# QSTL_Nano_D_Con_Micro_DSUB.net
KiCad netlist of a schematic drawn in Altium Designer
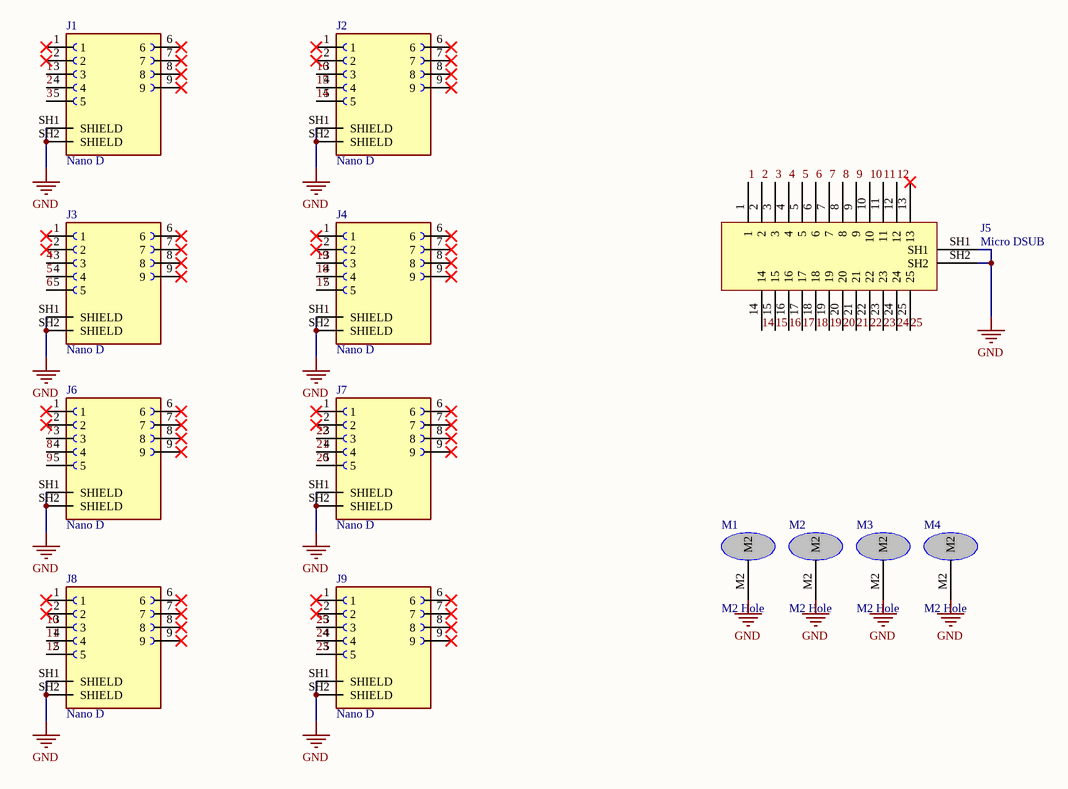
[diagram p0: QSTL_Nano_D_Con_Micro_DSUB.SchDoc]

(export (version "E")
  (design (tool "Eeschema 10.0.6"))
  (components
    (comp (ref "J1")
      (value "Nano D")
      (footprint "A29500-009")
      (description "https://www.digikey.ca/en/products/detail/omnetics/A29500-009/16614880")
      (libsource (lib "QSTL_Nano_D_Con_Micro_DSUB") (part "A29500-009"))
    )
    (comp (ref "J2")
      (value "Nano D")
      (footprint "A29500-009")
      (description "https://www.digikey.ca/en/products/detail/omnetics/A29500-009/16614880")
      (libsource (lib "QSTL_Nano_D_Con_Micro_DSUB") (part "A29500-009"))
    )
    (comp (ref "J3")
      (value "Nano D")
      (footprint "A29500-009")
      (description "https://www.digikey.ca/en/products/detail/omnetics/A29500-009/16614880")
      (libsource (lib "QSTL_Nano_D_Con_Micro_DSUB") (part "A29500-009"))
    )
    (comp (ref "J4")
      (value "Nano D")
      (footprint "A29500-009")
      (description "https://www.digikey.ca/en/products/detail/omnetics/A29500-009/16614880")
      (libsource (lib "QSTL_Nano_D_Con_Micro_DSUB") (part "A29500-009"))
    )
    (comp (ref "J5")
      (value "Micro DSUB")
      (footprint "380-025-113L001")
      (description "NorComp Plug Micro DSUB")
      (libsource (lib "QSTL_Nano_D_Con_Micro_DSUB") (part "380-025-113L001"))
    )
    (comp (ref "J6")
      (value "Nano D")
      (footprint "A29500-009")
      (description "https://www.digikey.ca/en/products/detail/omnetics/A29500-009/16614880")
      (libsource (lib "QSTL_Nano_D_Con_Micro_DSUB") (part "A29500-009"))
    )
    (comp (ref "J7")
      (value "Nano D")
      (footprint "A29500-009")
      (description "https://www.digikey.ca/en/products/detail/omnetics/A29500-009/16614880")
      (libsource (lib "QSTL_Nano_D_Con_Micro_DSUB") (part "A29500-009"))
    )
    (comp (ref "J8")
      (value "Nano D")
      (footprint "A29500-009")
      (description "https://www.digikey.ca/en/products/detail/omnetics/A29500-009/16614880")
      (libsource (lib "QSTL_Nano_D_Con_Micro_DSUB") (part "A29500-009"))
    )
    (comp (ref "J9")
      (value "Nano D")
      (footprint "A29500-009")
      (description "https://www.digikey.ca/en/products/detail/omnetics/A29500-009/16614880")
      (libsource (lib "QSTL_Nano_D_Con_Micro_DSUB") (part "A29500-009"))
    )
    (comp (ref "M1")
      (value "M2 Hole")
      (footprint "M2_Hole")
      (libsource (lib "QSTL_Nano_D_Con_Micro_DSUB") (part "M2_Hole"))
    )
    (comp (ref "M2")
      (value "M2 Hole")
      (footprint "M2_Hole")
      (libsource (lib "QSTL_Nano_D_Con_Micro_DSUB") (part "M2_Hole"))
    )
    (comp (ref "M3")
      (value "M2 Hole")
      (footprint "M2_Hole")
      (libsource (lib "QSTL_Nano_D_Con_Micro_DSUB") (part "M2_Hole"))
    )
    (comp (ref "M4")
      (value "M2 Hole")
      (footprint "M2_Hole")
      (libsource (lib "QSTL_Nano_D_Con_Micro_DSUB") (part "M2_Hole"))
    )
  )
  (nets
    (net (code "1") (name "/1") (class "Default")
      (node (ref "J1") (pin "3") (pinfunction "3_3") (pintype "passive"))
      (node (ref "J5") (pin "1") (pinfunction "1_1") (pintype "passive"))
    )
    (net (code "2") (name "/2") (class "Default")
      (node (ref "J1") (pin "4") (pinfunction "4_4") (pintype "passive"))
      (node (ref "J5") (pin "2") (pinfunction "2_2") (pintype "passive"))
    )
    (net (code "3") (name "/3") (class "Default")
      (node (ref "J1") (pin "5") (pinfunction "5_5") (pintype "passive"))
      (node (ref "J5") (pin "3") (pinfunction "3_3") (pintype "passive"))
    )
    (net (code "4") (name "/4") (class "Default")
      (node (ref "J3") (pin "3") (pinfunction "3_3") (pintype "passive"))
      (node (ref "J5") (pin "4") (pinfunction "4_4") (pintype "passive"))
    )
    (net (code "5") (name "/5") (class "Default")
      (node (ref "J3") (pin "4") (pinfunction "4_4") (pintype "passive"))
      (node (ref "J5") (pin "5") (pinfunction "5_5") (pintype "passive"))
    )
    (net (code "6") (name "/6") (class "Default")
      (node (ref "J3") (pin "5") (pinfunction "5_5") (pintype "passive"))
      (node (ref "J5") (pin "6") (pinfunction "6_6") (pintype "passive"))
    )
    (net (code "7") (name "/7") (class "Default")
      (node (ref "J5") (pin "7") (pinfunction "7_7") (pintype "passive"))
      (node (ref "J6") (pin "3") (pinfunction "3_3") (pintype "passive"))
    )
    (net (code "8") (name "/8") (class "Default")
      (node (ref "J5") (pin "8") (pinfunction "8_8") (pintype "passive"))
      (node (ref "J6") (pin "4") (pinfunction "4_4") (pintype "passive"))
    )
    (net (code "9") (name "/9") (class "Default")
      (node (ref "J5") (pin "9") (pinfunction "9_9") (pintype "passive"))
      (node (ref "J6") (pin "5") (pinfunction "5_5") (pintype "passive"))
    )
    (net (code "10") (name "/10") (class "Default")
      (node (ref "J5") (pin "10") (pinfunction "10_10") (pintype "passive"))
      (node (ref "J8") (pin "3") (pinfunction "3_3") (pintype "passive"))
    )
    (net (code "11") (name "/11") (class "Default")
      (node (ref "J5") (pin "11") (pinfunction "11_11") (pintype "passive"))
      (node (ref "J8") (pin "4") (pinfunction "4_4") (pintype "passive"))
    )
    (net (code "12") (name "/12") (class "Default")
      (node (ref "J5") (pin "12") (pinfunction "12_12") (pintype "passive"))
      (node (ref "J8") (pin "5") (pinfunction "5_5") (pintype "passive"))
    )
    (net (code "13") (name "/14") (class "Default")
      (node (ref "J2") (pin "5") (pinfunction "5_5") (pintype "passive"))
      (node (ref "J5") (pin "14") (pinfunction "14_14") (pintype "passive"))
    )
    (net (code "14") (name "/15") (class "Default")
      (node (ref "J2") (pin "4") (pinfunction "4_4") (pintype "passive"))
      (node (ref "J5") (pin "15") (pinfunction "15_15") (pintype "passive"))
    )
    (net (code "15") (name "/16") (class "Default")
      (node (ref "J2") (pin "3") (pinfunction "3_3") (pintype "passive"))
      (node (ref "J5") (pin "16") (pinfunction "16_16") (pintype "passive"))
    )
    (net (code "16") (name "/17") (class "Default")
      (node (ref "J4") (pin "5") (pinfunction "5_5") (pintype "passive"))
      (node (ref "J5") (pin "17") (pinfunction "17_17") (pintype "passive"))
    )
    (net (code "17") (name "/18") (class "Default")
      (node (ref "J4") (pin "4") (pinfunction "4_4") (pintype "passive"))
      (node (ref "J5") (pin "18") (pinfunction "18_18") (pintype "passive"))
    )
    (net (code "18") (name "/19") (class "Default")
      (node (ref "J4") (pin "3") (pinfunction "3_3") (pintype "passive"))
      (node (ref "J5") (pin "19") (pinfunction "19_19") (pintype "passive"))
    )
    (net (code "19") (name "/20") (class "Default")
      (node (ref "J5") (pin "20") (pinfunction "20_20") (pintype "passive"))
      (node (ref "J7") (pin "5") (pinfunction "5_5") (pintype "passive"))
    )
    (net (code "20") (name "/21") (class "Default")
      (node (ref "J5") (pin "21") (pinfunction "21_21") (pintype "passive"))
      (node (ref "J7") (pin "4") (pinfunction "4_4") (pintype "passive"))
    )
    (net (code "21") (name "/22") (class "Default")
      (node (ref "J5") (pin "22") (pinfunction "22_22") (pintype "passive"))
      (node (ref "J7") (pin "3") (pinfunction "3_3") (pintype "passive"))
    )
    (net (code "22") (name "/23") (class "Default")
      (node (ref "J5") (pin "23") (pinfunction "23_23") (pintype "passive"))
      (node (ref "J9") (pin "5") (pinfunction "5_5") (pintype "passive"))
    )
    (net (code "23") (name "/24") (class "Default")
      (node (ref "J5") (pin "24") (pinfunction "24_24") (pintype "passive"))
      (node (ref "J9") (pin "4") (pinfunction "4_4") (pintype "passive"))
    )
    (net (code "24") (name "/25") (class "Default")
      (node (ref "J5") (pin "25") (pinfunction "25_25") (pintype "passive"))
      (node (ref "J9") (pin "3") (pinfunction "3_3") (pintype "passive"))
    )
    (net (code "25") (name "GND") (class "Default")
      (node (ref "J1") (pin "SH1") (pinfunction "SHIELD_SH1") (pintype "passive"))
      (node (ref "J1") (pin "SH2") (pinfunction "SHIELD_SH2") (pintype "passive"))
      (node (ref "J2") (pin "SH1") (pinfunction "SHIELD_SH1") (pintype "passive"))
      (node (ref "J2") (pin "SH2") (pinfunction "SHIELD_SH2") (pintype "passive"))
      (node (ref "J3") (pin "SH1") (pinfunction "SHIELD_SH1") (pintype "passive"))
      (node (ref "J3") (pin "SH2") (pinfunction "SHIELD_SH2") (pintype "passive"))
      (node (ref "J4") (pin "SH1") (pinfunction "SHIELD_SH1") (pintype "passive"))
      (node (ref "J4") (pin "SH2") (pinfunction "SHIELD_SH2") (pintype "passive"))
      (node (ref "J5") (pin "SH1") (pinfunction "SH1_SH1") (pintype "passive"))
      (node (ref "J5") (pin "SH2") (pinfunction "SH2_SH2") (pintype "passive"))
      (node (ref "J6") (pin "SH1") (pinfunction "SHIELD_SH1") (pintype "passive"))
      (node (ref "J6") (pin "SH2") (pinfunction "SHIELD_SH2") (pintype "passive"))
      (node (ref "J7") (pin "SH1") (pinfunction "SHIELD_SH1") (pintype "passive"))
      (node (ref "J7") (pin "SH2") (pinfunction "SHIELD_SH2") (pintype "passive"))
      (node (ref "J8") (pin "SH1") (pinfunction "SHIELD_SH1") (pintype "passive"))
      (node (ref "J8") (pin "SH2") (pinfunction "SHIELD_SH2") (pintype "passive"))
      (node (ref "J9") (pin "SH1") (pinfunction "SHIELD_SH1") (pintype "passive"))
      (node (ref "J9") (pin "SH2") (pinfunction "SHIELD_SH2") (pintype "passive"))
      (node (ref "M1") (pin "M2") (pinfunction "M2_M2") (pintype "passive"))
      (node (ref "M2") (pin "M2") (pinfunction "M2_M2") (pintype "passive"))
      (node (ref "M3") (pin "M2") (pinfunction "M2_M2") (pintype "passive"))
      (node (ref "M4") (pin "M2") (pinfunction "M2_M2") (pintype "passive"))
    )
    (net (code "26") (name "unconnected-(J1-Pad1)") (class "Default")
      (node (ref "J1") (pin "1") (pinfunction "1_1") (pintype "passive+no_connect"))
    )
    (net (code "27") (name "unconnected-(J1-Pad2)") (class "Default")
      (node (ref "J1") (pin "2") (pinfunction "2_2") (pintype "passive+no_connect"))
    )
    (net (code "28") (name "unconnected-(J1-Pad6)") (class "Default")
      (node (ref "J1") (pin "6") (pinfunction "6_6") (pintype "passive+no_connect"))
    )
    (net (code "29") (name "unconnected-(J1-Pad7)") (class "Default")
      (node (ref "J1") (pin "7") (pinfunction "7_7") (pintype "passive+no_connect"))
    )
    (net (code "30") (name "unconnected-(J1-Pad8)") (class "Default")
      (node (ref "J1") (pin "8") (pinfunction "8_8") (pintype "passive+no_connect"))
    )
    (net (code "31") (name "unconnected-(J1-Pad9)") (class "Default")
      (node (ref "J1") (pin "9") (pinfunction "9_9") (pintype "passive+no_connect"))
    )
    (net (code "32") (name "unconnected-(J2-Pad1)") (class "Default")
      (node (ref "J2") (pin "1") (pinfunction "1_1") (pintype "passive+no_connect"))
    )
    (net (code "33") (name "unconnected-(J2-Pad2)") (class "Default")
      (node (ref "J2") (pin "2") (pinfunction "2_2") (pintype "passive+no_connect"))
    )
    (net (code "34") (name "unconnected-(J2-Pad6)") (class "Default")
      (node (ref "J2") (pin "6") (pinfunction "6_6") (pintype "passive+no_connect"))
    )
    (net (code "35") (name "unconnected-(J2-Pad7)") (class "Default")
      (node (ref "J2") (pin "7") (pinfunction "7_7") (pintype "passive+no_connect"))
    )
    (net (code "36") (name "unconnected-(J2-Pad8)") (class "Default")
      (node (ref "J2") (pin "8") (pinfunction "8_8") (pintype "passive+no_connect"))
    )
    (net (code "37") (name "unconnected-(J2-Pad9)") (class "Default")
      (node (ref "J2") (pin "9") (pinfunction "9_9") (pintype "passive+no_connect"))
    )
    (net (code "38") (name "unconnected-(J3-Pad1)") (class "Default")
      (node (ref "J3") (pin "1") (pinfunction "1_1") (pintype "passive+no_connect"))
    )
    (net (code "39") (name "unconnected-(J3-Pad2)") (class "Default")
      (node (ref "J3") (pin "2") (pinfunction "2_2") (pintype "passive+no_connect"))
    )
    (net (code "40") (name "unconnected-(J3-Pad6)") (class "Default")
      (node (ref "J3") (pin "6") (pinfunction "6_6") (pintype "passive+no_connect"))
    )
    (net (code "41") (name "unconnected-(J3-Pad7)") (class "Default")
      (node (ref "J3") (pin "7") (pinfunction "7_7") (pintype "passive+no_connect"))
    )
    (net (code "42") (name "unconnected-(J3-Pad8)") (class "Default")
      (node (ref "J3") (pin "8") (pinfunction "8_8") (pintype "passive+no_connect"))
    )
    (net (code "43") (name "unconnected-(J3-Pad9)") (class "Default")
      (node (ref "J3") (pin "9") (pinfunction "9_9") (pintype "passive+no_connect"))
    )
    (net (code "44") (name "unconnected-(J4-Pad1)") (class "Default")
      (node (ref "J4") (pin "1") (pinfunction "1_1") (pintype "passive+no_connect"))
    )
    (net (code "45") (name "unconnected-(J4-Pad2)") (class "Default")
      (node (ref "J4") (pin "2") (pinfunction "2_2") (pintype "passive+no_connect"))
    )
    (net (code "46") (name "unconnected-(J4-Pad6)") (class "Default")
      (node (ref "J4") (pin "6") (pinfunction "6_6") (pintype "passive+no_connect"))
    )
    (net (code "47") (name "unconnected-(J4-Pad7)") (class "Default")
      (node (ref "J4") (pin "7") (pinfunction "7_7") (pintype "passive+no_connect"))
    )
    (net (code "48") (name "unconnected-(J4-Pad8)") (class "Default")
      (node (ref "J4") (pin "8") (pinfunction "8_8") (pintype "passive+no_connect"))
    )
    (net (code "49") (name "unconnected-(J4-Pad9)") (class "Default")
      (node (ref "J4") (pin "9") (pinfunction "9_9") (pintype "passive+no_connect"))
    )
    (net (code "50") (name "unconnected-(J5-Pad13)") (class "Default")
      (node (ref "J5") (pin "13") (pinfunction "13_13") (pintype "passive+no_connect"))
    )
    (net (code "51") (name "unconnected-(J6-Pad1)") (class "Default")
      (node (ref "J6") (pin "1") (pinfunction "1_1") (pintype "passive+no_connect"))
    )
    (net (code "52") (name "unconnected-(J6-Pad2)") (class "Default")
      (node (ref "J6") (pin "2") (pinfunction "2_2") (pintype "passive+no_connect"))
    )
    (net (code "53") (name "unconnected-(J6-Pad6)") (class "Default")
      (node (ref "J6") (pin "6") (pinfunction "6_6") (pintype "passive+no_connect"))
    )
    (net (code "54") (name "unconnected-(J6-Pad7)") (class "Default")
      (node (ref "J6") (pin "7") (pinfunction "7_7") (pintype "passive+no_connect"))
    )
    (net (code "55") (name "unconnected-(J6-Pad8)") (class "Default")
      (node (ref "J6") (pin "8") (pinfunction "8_8") (pintype "passive+no_connect"))
    )
    (net (code "56") (name "unconnected-(J6-Pad9)") (class "Default")
      (node (ref "J6") (pin "9") (pinfunction "9_9") (pintype "passive+no_connect"))
    )
    (net (code "57") (name "unconnected-(J7-Pad1)") (class "Default")
      (node (ref "J7") (pin "1") (pinfunction "1_1") (pintype "passive+no_connect"))
    )
    (net (code "58") (name "unconnected-(J7-Pad2)") (class "Default")
      (node (ref "J7") (pin "2") (pinfunction "2_2") (pintype "passive+no_connect"))
    )
    (net (code "59") (name "unconnected-(J7-Pad6)") (class "Default")
      (node (ref "J7") (pin "6") (pinfunction "6_6") (pintype "passive+no_connect"))
    )
    (net (code "60") (name "unconnected-(J7-Pad7)") (class "Default")
      (node (ref "J7") (pin "7") (pinfunction "7_7") (pintype "passive+no_connect"))
    )
    (net (code "61") (name "unconnected-(J7-Pad8)") (class "Default")
      (node (ref "J7") (pin "8") (pinfunction "8_8") (pintype "passive+no_connect"))
    )
    (net (code "62") (name "unconnected-(J7-Pad9)") (class "Default")
      (node (ref "J7") (pin "9") (pinfunction "9_9") (pintype "passive+no_connect"))
    )
    (net (code "63") (name "unconnected-(J8-Pad1)") (class "Default")
      (node (ref "J8") (pin "1") (pinfunction "1_1") (pintype "passive+no_connect"))
    )
    (net (code "64") (name "unconnected-(J8-Pad2)") (class "Default")
      (node (ref "J8") (pin "2") (pinfunction "2_2") (pintype "passive+no_connect"))
    )
    (net (code "65") (name "unconnected-(J8-Pad6)") (class "Default")
      (node (ref "J8") (pin "6") (pinfunction "6_6") (pintype "passive+no_connect"))
    )
    (net (code "66") (name "unconnected-(J8-Pad7)") (class "Default")
      (node (ref "J8") (pin "7") (pinfunction "7_7") (pintype "passive+no_connect"))
    )
    (net (code "67") (name "unconnected-(J8-Pad8)") (class "Default")
      (node (ref "J8") (pin "8") (pinfunction "8_8") (pintype "passive+no_connect"))
    )
    (net (code "68") (name "unconnected-(J8-Pad9)") (class "Default")
      (node (ref "J8") (pin "9") (pinfunction "9_9") (pintype "passive+no_connect"))
    )
    (net (code "69") (name "unconnected-(J9-Pad1)") (class "Default")
      (node (ref "J9") (pin "1") (pinfunction "1_1") (pintype "passive+no_connect"))
    )
    (net (code "70") (name "unconnected-(J9-Pad2)") (class "Default")
      (node (ref "J9") (pin "2") (pinfunction "2_2") (pintype "passive+no_connect"))
    )
    (net (code "71") (name "unconnected-(J9-Pad6)") (class "Default")
      (node (ref "J9") (pin "6") (pinfunction "6_6") (pintype "passive+no_connect"))
    )
    (net (code "72") (name "unconnected-(J9-Pad7)") (class "Default")
      (node (ref "J9") (pin "7") (pinfunction "7_7") (pintype "passive+no_connect"))
    )
    (net (code "73") (name "unconnected-(J9-Pad8)") (class "Default")
      (node (ref "J9") (pin "8") (pinfunction "8_8") (pintype "passive+no_connect"))
    )
    (net (code "74") (name "unconnected-(J9-Pad9)") (class "Default")
      (node (ref "J9") (pin "9") (pinfunction "9_9") (pintype "passive+no_connect"))
    )
  )
)
